# RoasterInterface.net
KiCad netlist of a schematic drawn in EAGLE
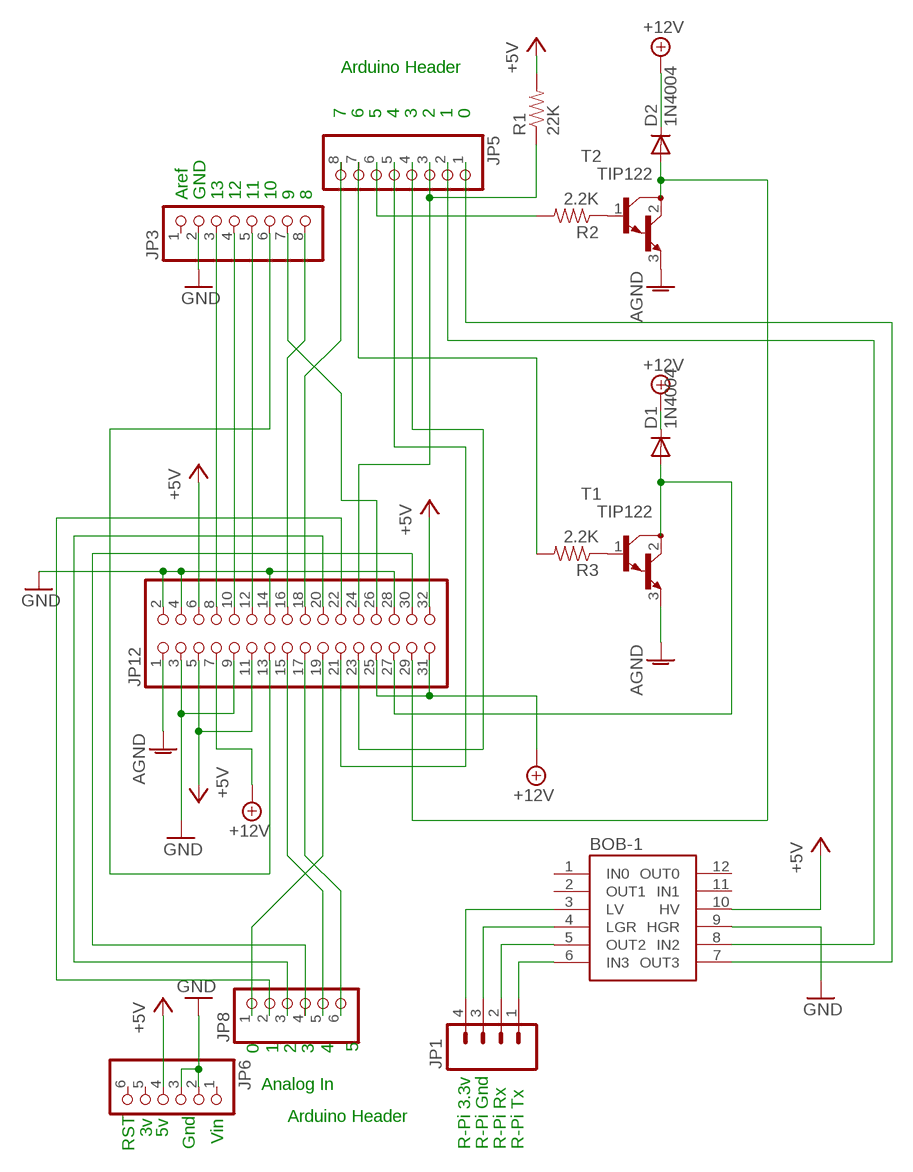
[diagram p0: schematic, sheet 1]

(export (version "E")
  (design (tool "Eeschema 10.0.6"))
  (components
    (comp (ref "BOB-1")
      (value "BOB-08745DEFAULT")
      (footprint "eagle-import:5X6BOB")
      (libsource (lib "eagle-import") (part "BOB-08745DEFAULT"))
    )
    (comp (ref "D1")
      (value "1N4004")
      (footprint "eagle-import:DO41-10")
      (libsource (lib "eagle-import") (part "1N4004"))
    )
    (comp (ref "D2")
      (value "1N4004")
      (footprint "eagle-import:DO41-10")
      (libsource (lib "eagle-import") (part "1N4004"))
    )
    (comp (ref "JP1")
      (value "M04LOCK")
      (footprint "eagle-import:1X04_LOCK")
      (libsource (lib "eagle-import") (part "M04LOCK"))
    )
    (comp (ref "JP3")
      (value "PINHD-1X8CLEANBIG")
      (footprint "eagle-import:1X08-CLEANBIG")
      (libsource (lib "eagle-import") (part "PINHD-1X8CLEANBIG"))
    )
    (comp (ref "JP5")
      (value "PINHD-1X8CLEANBIG")
      (footprint "eagle-import:1X08-CLEANBIG")
      (libsource (lib "eagle-import") (part "PINHD-1X8CLEANBIG"))
    )
    (comp (ref "JP6")
      (value "PINHD-1X6CB")
      (footprint "eagle-import:1X06-CLEANBIG")
      (libsource (lib "eagle-import") (part "PINHD-1X6CB"))
    )
    (comp (ref "JP8")
      (value "PINHD-1X6CB")
      (footprint "eagle-import:1X06-CLEANBIG")
      (libsource (lib "eagle-import") (part "PINHD-1X6CB"))
    )
    (comp (ref "JP12")
      (value "PINHD-2X16")
      (footprint "eagle-import:2X16")
      (libsource (lib "eagle-import") (part "PINHD-2X16"))
    )
    (comp (ref "R1")
      (value "22K")
      (footprint "eagle-import:AXIAL-0.4")
      (libsource (lib "eagle-import") (part "RESISTORPTH-1/4W"))
    )
    (comp (ref "R2")
      (value "2.2K")
      (footprint "eagle-import:AXIAL-0.4")
      (libsource (lib "eagle-import") (part "RESISTORPTH-1/4W"))
    )
    (comp (ref "R3")
      (value "2.2K")
      (footprint "eagle-import:AXIAL-0.4")
      (libsource (lib "eagle-import") (part "RESISTORPTH-1/4W"))
    )
    (comp (ref "T1")
      (value "TIP122")
      (footprint "eagle-import:TO220")
      (libsource (lib "eagle-import") (part "TIP122"))
    )
    (comp (ref "T2")
      (value "TIP122")
      (footprint "eagle-import:TO220")
      (libsource (lib "eagle-import") (part "TIP122"))
    )
  )
  (nets
    (net (code "1") (name "+5V") (class "Default")
      (node (ref "BOB-1") (pin "10") (pinfunction "HV_10") (pintype "bidirectional"))
      (node (ref "JP12") (pin "11") (pinfunction "11_11") (pintype "passive"))
      (node (ref "JP12") (pin "32") (pinfunction "32_32") (pintype "passive"))
      (node (ref "JP12") (pin "5") (pinfunction "5_5") (pintype "passive"))
      (node (ref "JP12") (pin "6") (pinfunction "6_6") (pintype "passive"))
      (node (ref "JP6") (pin "4") (pinfunction "4_4") (pintype "passive"))
      (node (ref "R1") (pin "P$2") (pinfunction "2_P$2") (pintype "passive"))
    )
    (net (code "2") (name "+12V") (class "Default")
      (node (ref "D1") (pin "C") (pinfunction "C_C") (pintype "passive"))
      (node (ref "D2") (pin "C") (pinfunction "C_C") (pintype "passive"))
      (node (ref "JP12") (pin "25") (pinfunction "25_25") (pintype "passive"))
      (node (ref "JP12") (pin "31") (pinfunction "31_31") (pintype "passive"))
      (node (ref "JP12") (pin "7") (pinfunction "7_7") (pintype "passive"))
    )
    (net (code "3") (name "AGND") (class "Default")
      (node (ref "JP12") (pin "1") (pinfunction "1_1") (pintype "passive"))
      (node (ref "T1") (pin "3") (pinfunction "E_3") (pintype "passive"))
      (node (ref "T2") (pin "3") (pinfunction "E_3") (pintype "passive"))
    )
    (net (code "4") (name "GND") (class "Default")
      (node (ref "BOB-1") (pin "9") (pinfunction "HGR_9") (pintype "bidirectional"))
      (node (ref "JP12") (pin "14") (pinfunction "14_14") (pintype "passive"))
      (node (ref "JP12") (pin "2") (pinfunction "2_2") (pintype "passive"))
      (node (ref "JP12") (pin "28") (pinfunction "28_28") (pintype "passive"))
      (node (ref "JP12") (pin "3") (pinfunction "3_3") (pintype "passive"))
      (node (ref "JP12") (pin "4") (pinfunction "4_4") (pintype "passive"))
      (node (ref "JP12") (pin "9") (pinfunction "9_9") (pintype "passive"))
      (node (ref "JP3") (pin "2") (pinfunction "2_2") (pintype "passive"))
      (node (ref "JP6") (pin "2") (pinfunction "2_2") (pintype "passive"))
      (node (ref "JP6") (pin "3") (pinfunction "3_3") (pintype "passive"))
    )
    (net (code "5") (name "Net-(BOB-1-IN2)") (class "Default")
      (node (ref "BOB-1") (pin "8") (pinfunction "IN2_8") (pintype "bidirectional"))
      (node (ref "JP5") (pin "2") (pinfunction "2_2") (pintype "passive"))
    )
    (net (code "6") (name "Net-(BOB-1-IN3)") (class "Default")
      (node (ref "BOB-1") (pin "6") (pinfunction "IN3_6") (pintype "bidirectional"))
      (node (ref "JP1") (pin "1") (pinfunction "1_1") (pintype "passive"))
    )
    (net (code "7") (name "Net-(BOB-1-LGR)") (class "Default")
      (node (ref "BOB-1") (pin "4") (pinfunction "LGR_4") (pintype "bidirectional"))
      (node (ref "JP1") (pin "3") (pinfunction "3_3") (pintype "passive"))
    )
    (net (code "8") (name "Net-(BOB-1-LV)") (class "Default")
      (node (ref "BOB-1") (pin "3") (pinfunction "LV_3") (pintype "bidirectional"))
      (node (ref "JP1") (pin "4") (pinfunction "4_4") (pintype "passive"))
    )
    (net (code "9") (name "Net-(BOB-1-OUT2)") (class "Default")
      (node (ref "BOB-1") (pin "5") (pinfunction "OUT2_5") (pintype "bidirectional"))
      (node (ref "JP1") (pin "2") (pinfunction "2_2") (pintype "passive"))
    )
    (net (code "10") (name "Net-(BOB-1-OUT3)") (class "Default")
      (node (ref "BOB-1") (pin "7") (pinfunction "OUT3_7") (pintype "bidirectional"))
      (node (ref "JP5") (pin "1") (pinfunction "1_1") (pintype "passive"))
    )
    (net (code "11") (name "Net-(JP12-Pad8)") (class "Default")
      (node (ref "JP12") (pin "8") (pinfunction "8_8") (pintype "passive"))
      (node (ref "JP3") (pin "3") (pinfunction "3_3") (pintype "passive"))
    )
    (net (code "12") (name "Net-(JP12-Pad10)") (class "Default")
      (node (ref "JP12") (pin "10") (pinfunction "10_10") (pintype "passive"))
      (node (ref "JP3") (pin "4") (pinfunction "4_4") (pintype "passive"))
    )
    (net (code "13") (name "Net-(JP12-Pad12)") (class "Default")
      (node (ref "JP12") (pin "12") (pinfunction "12_12") (pintype "passive"))
      (node (ref "JP3") (pin "5") (pinfunction "5_5") (pintype "passive"))
    )
    (net (code "14") (name "Net-(JP12-Pad13)") (class "Default")
      (node (ref "JP12") (pin "13") (pinfunction "13_13") (pintype "passive"))
      (node (ref "JP3") (pin "6") (pinfunction "6_6") (pintype "passive"))
    )
    (net (code "15") (name "Net-(JP12-Pad15)") (class "Default")
      (node (ref "JP12") (pin "15") (pinfunction "15_15") (pintype "passive"))
      (node (ref "JP8") (pin "5") (pinfunction "5_5") (pintype "passive"))
    )
    (net (code "16") (name "Net-(JP12-Pad16)") (class "Default")
      (node (ref "JP12") (pin "16") (pinfunction "16_16") (pintype "passive"))
      (node (ref "JP3") (pin "8") (pinfunction "8_8") (pintype "passive"))
    )
    (net (code "17") (name "Net-(JP12-Pad17)") (class "Default")
      (node (ref "JP12") (pin "17") (pinfunction "17_17") (pintype "passive"))
      (node (ref "JP8") (pin "6") (pinfunction "6_6") (pintype "passive"))
    )
    (net (code "18") (name "Net-(JP12-Pad18)") (class "Default")
      (node (ref "JP12") (pin "18") (pinfunction "18_18") (pintype "passive"))
      (node (ref "JP5") (pin "8") (pinfunction "8_8") (pintype "passive"))
    )
    (net (code "19") (name "Net-(JP12-Pad19)") (class "Default")
      (node (ref "JP12") (pin "19") (pinfunction "19_19") (pintype "passive"))
      (node (ref "JP8") (pin "1") (pinfunction "1_1") (pintype "passive"))
    )
    (net (code "20") (name "Net-(JP12-Pad20)") (class "Default")
      (node (ref "JP12") (pin "20") (pinfunction "20_20") (pintype "passive"))
      (node (ref "JP8") (pin "3") (pinfunction "3_3") (pintype "passive"))
    )
    (net (code "21") (name "Net-(JP12-Pad21)") (class "Default")
      (node (ref "JP12") (pin "21") (pinfunction "21_21") (pintype "passive"))
      (node (ref "JP5") (pin "5") (pinfunction "5_5") (pintype "passive"))
    )
    (net (code "22") (name "Net-(JP12-Pad22)") (class "Default")
      (node (ref "JP12") (pin "22") (pinfunction "22_22") (pintype "passive"))
      (node (ref "JP8") (pin "2") (pinfunction "2_2") (pintype "passive"))
    )
    (net (code "23") (name "Net-(JP12-Pad23)") (class "Default")
      (node (ref "JP12") (pin "23") (pinfunction "23_23") (pintype "passive"))
      (node (ref "JP5") (pin "4") (pinfunction "4_4") (pintype "passive"))
    )
    (net (code "24") (name "Net-(JP12-Pad26)") (class "Default")
      (node (ref "JP12") (pin "26") (pinfunction "26_26") (pintype "passive"))
      (node (ref "JP3") (pin "7") (pinfunction "7_7") (pintype "passive"))
    )
    (net (code "25") (name "Net-(JP12-Pad30)") (class "Default")
      (node (ref "JP12") (pin "30") (pinfunction "30_30") (pintype "passive"))
      (node (ref "JP8") (pin "4") (pinfunction "4_4") (pintype "passive"))
    )
    (net (code "26") (name "Net-(R1-1)") (class "Default")
      (node (ref "JP12") (pin "24") (pinfunction "24_24") (pintype "passive"))
      (node (ref "JP5") (pin "3") (pinfunction "3_3") (pintype "passive"))
      (node (ref "R1") (pin "P$1") (pinfunction "1_P$1") (pintype "passive"))
    )
    (net (code "27") (name "Net-(R2-1)") (class "Default")
      (node (ref "R2") (pin "P$1") (pinfunction "1_P$1") (pintype "passive"))
      (node (ref "T2") (pin "1") (pinfunction "B_1") (pintype "passive"))
    )
    (net (code "28") (name "Net-(R2-2)") (class "Default")
      (node (ref "JP5") (pin "6") (pinfunction "6_6") (pintype "passive"))
      (node (ref "R2") (pin "P$2") (pinfunction "2_P$2") (pintype "passive"))
    )
    (net (code "29") (name "Net-(R3-1)") (class "Default")
      (node (ref "R3") (pin "P$1") (pinfunction "1_P$1") (pintype "passive"))
      (node (ref "T1") (pin "1") (pinfunction "B_1") (pintype "passive"))
    )
    (net (code "30") (name "Net-(R3-2)") (class "Default")
      (node (ref "JP5") (pin "7") (pinfunction "7_7") (pintype "passive"))
      (node (ref "R3") (pin "P$2") (pinfunction "2_P$2") (pintype "passive"))
    )
    (net (code "31") (name "Net-(T1-C)") (class "Default")
      (node (ref "D1") (pin "A") (pinfunction "A_A") (pintype "passive"))
      (node (ref "JP12") (pin "27") (pinfunction "27_27") (pintype "passive"))
      (node (ref "T1") (pin "2") (pinfunction "C_2") (pintype "passive"))
    )
    (net (code "32") (name "Net-(T2-C)") (class "Default")
      (node (ref "D2") (pin "A") (pinfunction "A_A") (pintype "passive"))
      (node (ref "JP12") (pin "29") (pinfunction "29_29") (pintype "passive"))
      (node (ref "T2") (pin "2") (pinfunction "C_2") (pintype "passive"))
    )
    (net (code "33") (name "unconnected-(BOB-1-IN0-Pad1)") (class "Default")
      (node (ref "BOB-1") (pin "1") (pinfunction "IN0_1") (pintype "bidirectional"))
    )
    (net (code "34") (name "unconnected-(BOB-1-IN1-Pad11)") (class "Default")
      (node (ref "BOB-1") (pin "11") (pinfunction "IN1_11") (pintype "bidirectional"))
    )
    (net (code "35") (name "unconnected-(BOB-1-OUT0-Pad12)") (class "Default")
      (node (ref "BOB-1") (pin "12") (pinfunction "OUT0_12") (pintype "bidirectional"))
    )
    (net (code "36") (name "unconnected-(BOB-1-OUT1-Pad2)") (class "Default")
      (node (ref "BOB-1") (pin "2") (pinfunction "OUT1_2") (pintype "bidirectional"))
    )
    (net (code "37") (name "unconnected-(JP3-Pad1)") (class "Default")
      (node (ref "JP3") (pin "1") (pinfunction "1_1") (pintype "passive"))
    )
    (net (code "38") (name "unconnected-(JP6-Pad1)") (class "Default")
      (node (ref "JP6") (pin "1") (pinfunction "1_1") (pintype "passive"))
    )
    (net (code "39") (name "unconnected-(JP6-Pad5)") (class "Default")
      (node (ref "JP6") (pin "5") (pinfunction "5_5") (pintype "passive"))
    )
    (net (code "40") (name "unconnected-(JP6-Pad6)") (class "Default")
      (node (ref "JP6") (pin "6") (pinfunction "6_6") (pintype "passive"))
    )
  )
)
